# rf24-prueba12-F.net
KiCad netlist of a schematic drawn in EAGLE
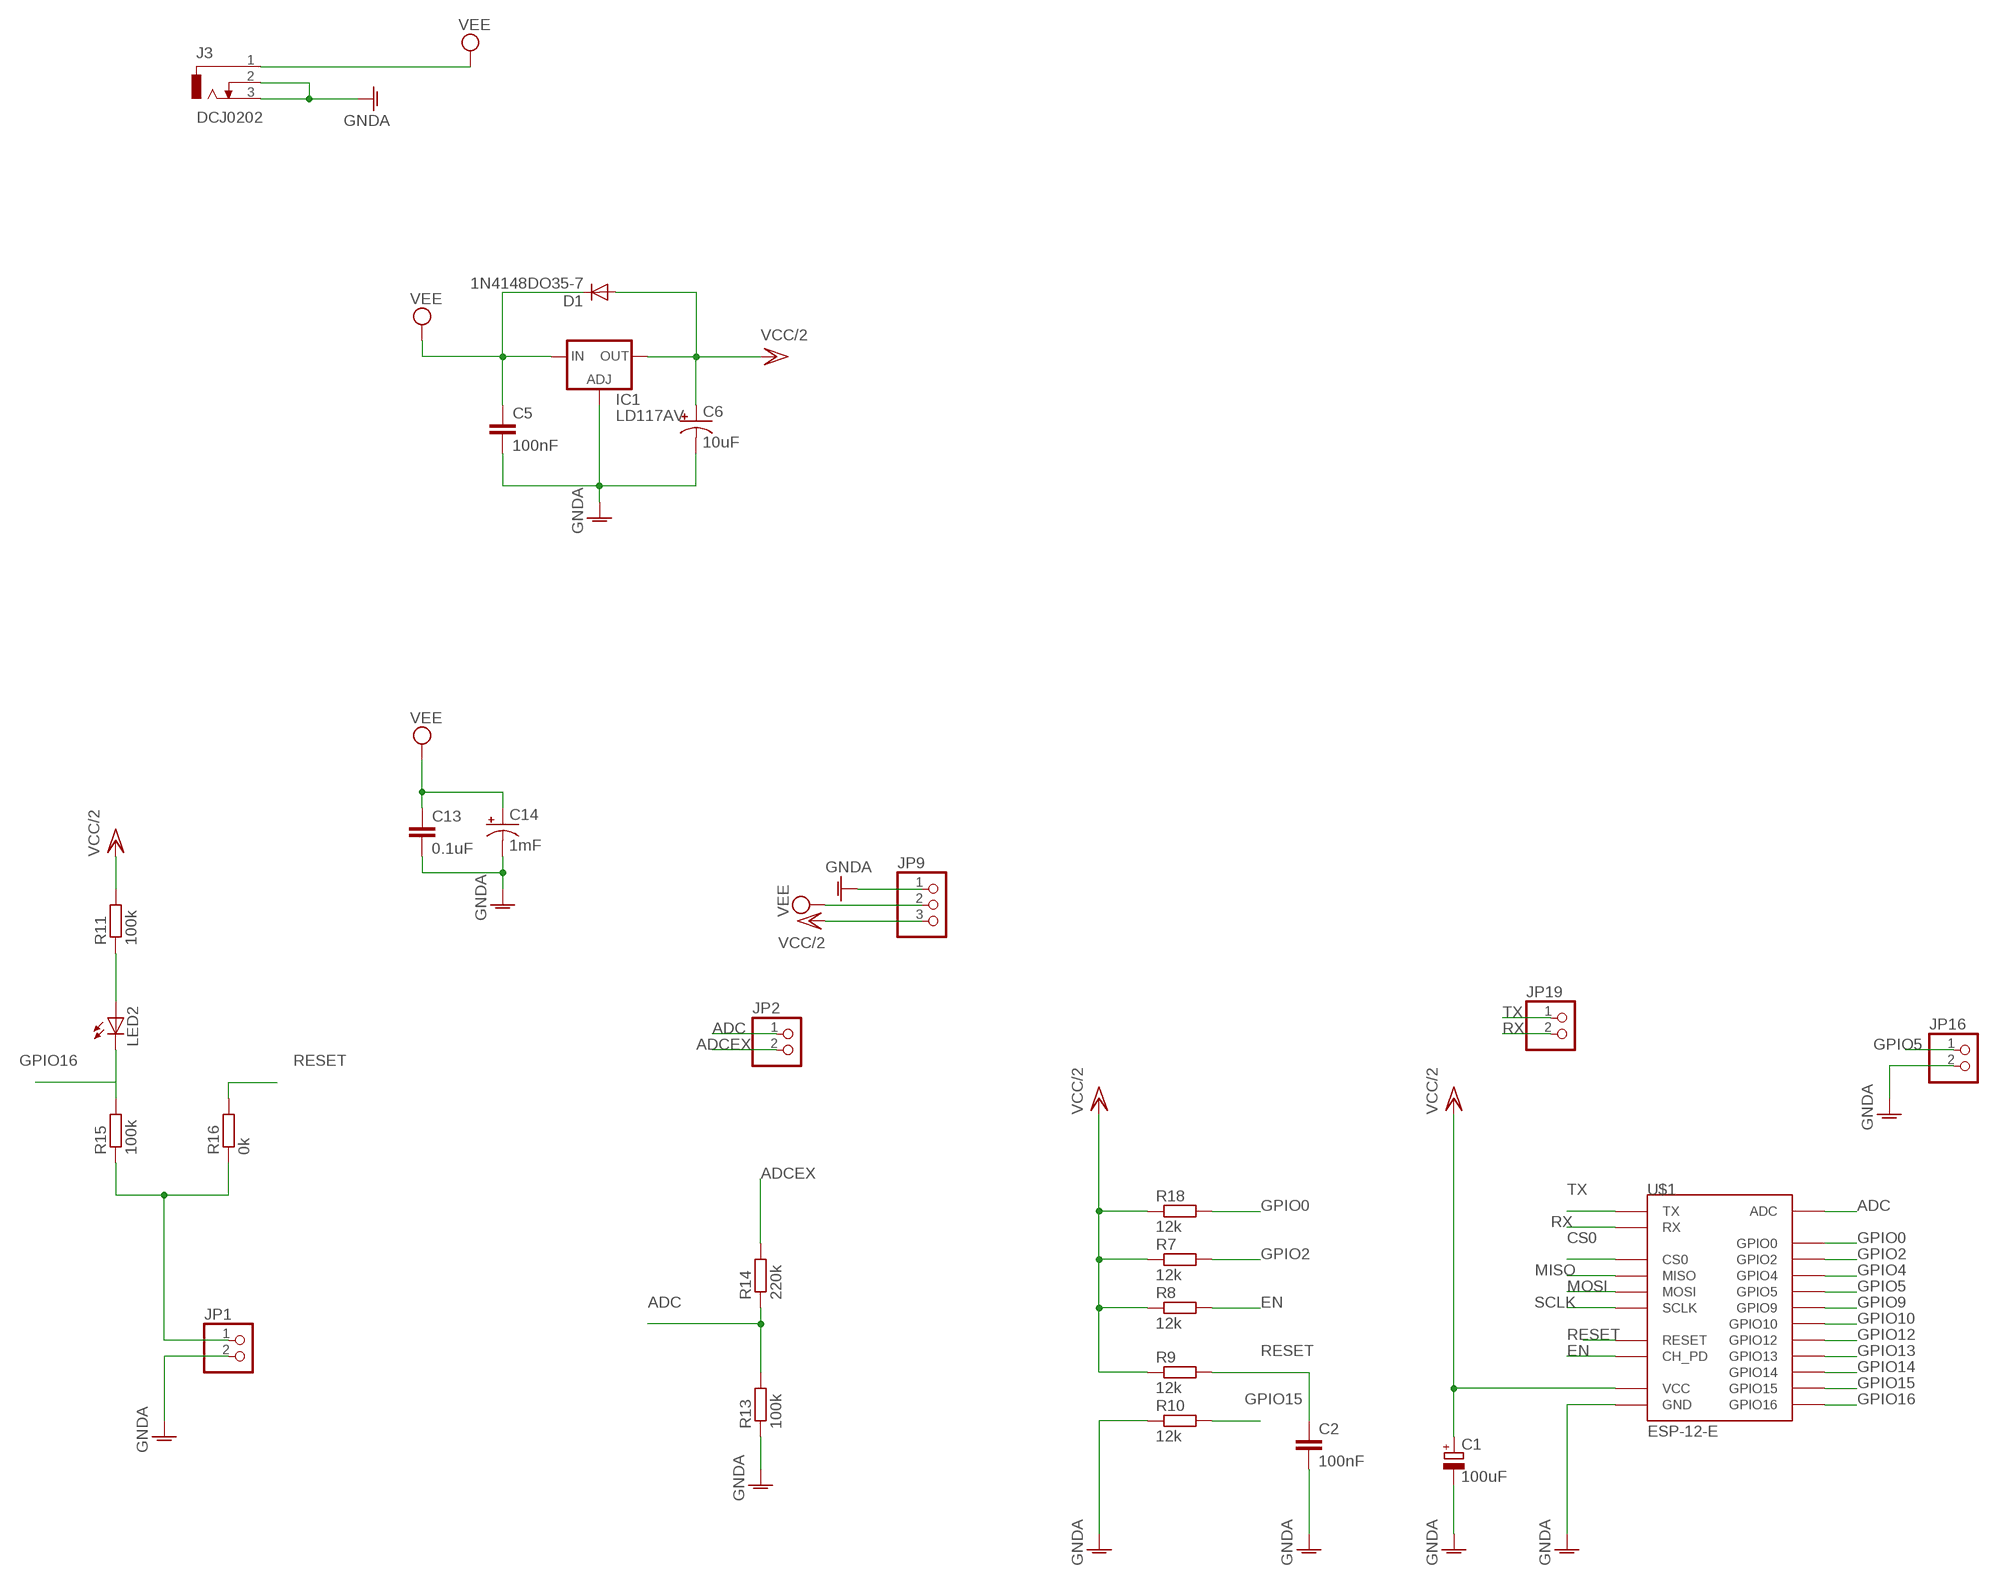
[diagram p0: schematic, sheet 1, part 1 of 2]
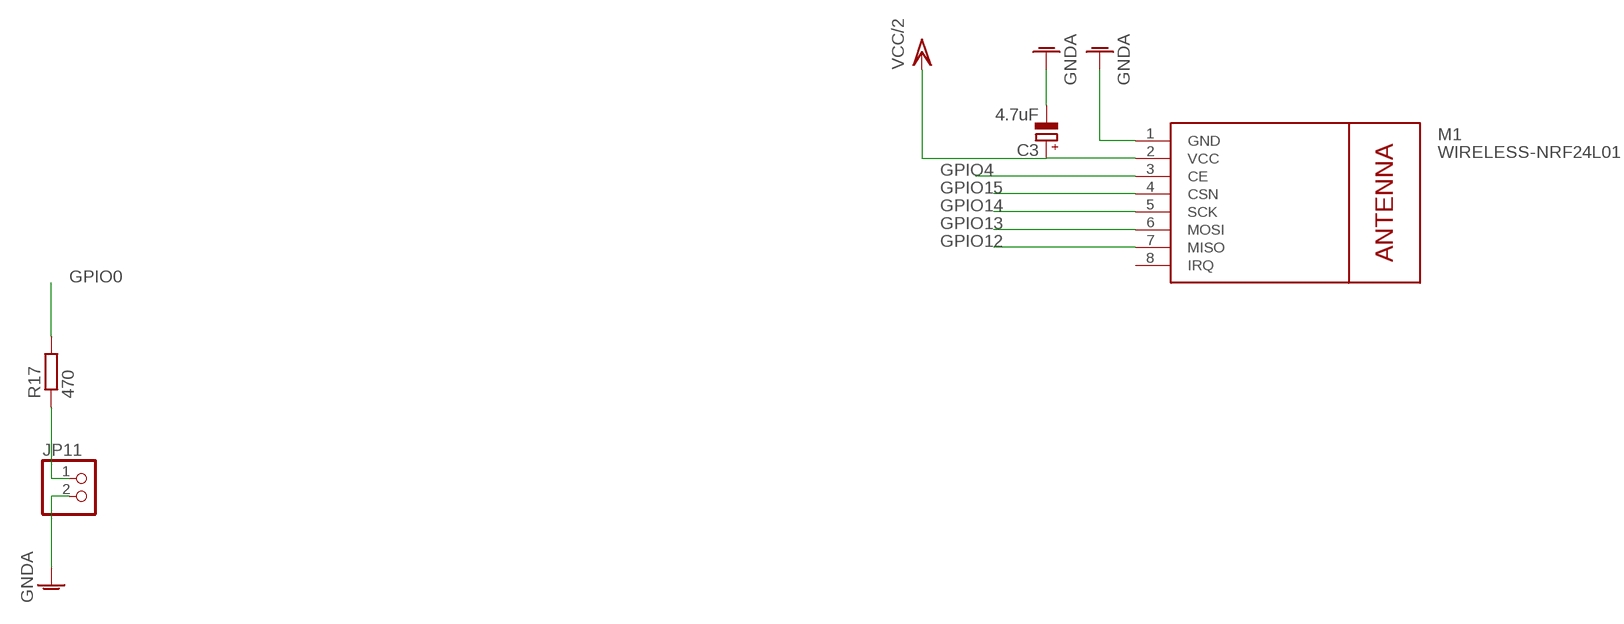
[diagram p1: schematic, sheet 1, part 2 of 2]

(export (version "E")
  (design (tool "Eeschema 10.0.6"))
  (components
    (comp (ref "C1")
      (value "100uF")
      (footprint "eagle-import:TT5D7")
      (libsource (lib "eagle-import") (part "CPOL-EUTT5D7"))
    )
    (comp (ref "C2")
      (value "100nF")
      (footprint "eagle-import:C025-024X044")
      (libsource (lib "eagle-import") (part "C-EU025-024X044"))
    )
    (comp (ref "C3")
      (value "4.7uF")
      (footprint "eagle-import:TT5D7")
      (libsource (lib "eagle-import") (part "CPOL-EUTT5D7"))
    )
    (comp (ref "C5")
      (value "100nF")
      (footprint "eagle-import:C025-025X050")
      (libsource (lib "eagle-import") (part "C-EU025-025X050"))
    )
    (comp (ref "C6")
      (value "10uF")
      (footprint "eagle-import:E2,5-6E")
      (libsource (lib "eagle-import") (part "CPOL-USE2,5-6E"))
    )
    (comp (ref "C13")
      (value "0.1uF")
      (footprint "eagle-import:C025-025X050")
      (libsource (lib "eagle-import") (part "C-EU025-025X050"))
    )
    (comp (ref "C14")
      (value "1mF")
      (footprint "eagle-import:E2,5-6E")
      (libsource (lib "eagle-import") (part "CPOL-USE2,5-6E"))
    )
    (comp (ref "D1")
      (value "1N4148DO35-7")
      (footprint "eagle-import:DO35-7")
      (libsource (lib "eagle-import") (part "1N4148DO35-7"))
    )
    (comp (ref "IC1")
      (value "LD117AV")
      (footprint "eagle-import:TO220L1")
      (libsource (lib "eagle-import") (part "LD117A?V"))
    )
    (comp (ref "J3")
      (value "DCJ0202")
      (footprint "eagle-import:DCJ0202")
      (libsource (lib "eagle-import") (part "DCJ0202"))
    )
    (comp (ref "JP1")
      (value "PINHD-1X2")
      (footprint "eagle-import:1X02")
      (libsource (lib "eagle-import") (part "PINHD-1X2"))
    )
    (comp (ref "JP2")
      (value "PINHD-1X2")
      (footprint "eagle-import:1X02")
      (libsource (lib "eagle-import") (part "PINHD-1X2"))
    )
    (comp (ref "JP9")
      (value "PINHD-1X3")
      (footprint "eagle-import:1X03")
      (libsource (lib "eagle-import") (part "PINHD-1X3"))
    )
    (comp (ref "JP11")
      (value "PINHD-1X2")
      (footprint "eagle-import:1X02")
      (libsource (lib "eagle-import") (part "PINHD-1X2"))
    )
    (comp (ref "JP16")
      (value "PINHD-1X2")
      (footprint "eagle-import:1X02")
      (libsource (lib "eagle-import") (part "PINHD-1X2"))
    )
    (comp (ref "JP19")
      (value "PINHD-1X2")
      (footprint "eagle-import:1X02")
      (libsource (lib "eagle-import") (part "PINHD-1X2"))
    )
    (comp (ref "LED2")
      (value "LED3MM")
      (footprint "eagle-import:LED3MM")
      (libsource (lib "eagle-import") (part "LED3MM"))
    )
    (comp (ref "M1")
      (value "WIRELESS-NRF24L01")
      (footprint "eagle-import:WIRELESS-NRF24L01")
      (libsource (lib "eagle-import") (part "WIRELESS-NRF24L01"))
    )
    (comp (ref "R7")
      (value "12k")
      (footprint "eagle-import:0207_7")
      (libsource (lib "eagle-import") (part "R-EU_0207/7"))
    )
    (comp (ref "R8")
      (value "12k")
      (footprint "eagle-import:0207_7")
      (libsource (lib "eagle-import") (part "R-EU_0207/7"))
    )
    (comp (ref "R9")
      (value "12k")
      (footprint "eagle-import:0207_7")
      (libsource (lib "eagle-import") (part "R-EU_0207/7"))
    )
    (comp (ref "R10")
      (value "12k")
      (footprint "eagle-import:0207_7")
      (libsource (lib "eagle-import") (part "R-EU_0207/7"))
    )
    (comp (ref "R11")
      (value "100k")
      (footprint "eagle-import:0207_7")
      (libsource (lib "eagle-import") (part "R-EU_0207/7"))
    )
    (comp (ref "R13")
      (value "100k")
      (footprint "eagle-import:0207_7")
      (libsource (lib "eagle-import") (part "R-EU_0207/7"))
    )
    (comp (ref "R14")
      (value "220k")
      (footprint "eagle-import:0207_7")
      (libsource (lib "eagle-import") (part "R-EU_0207/7"))
    )
    (comp (ref "R15")
      (value "100k")
      (footprint "eagle-import:0207_7")
      (libsource (lib "eagle-import") (part "R-EU_0207/7"))
    )
    (comp (ref "R16")
      (value "0k")
      (footprint "eagle-import:0207_7")
      (libsource (lib "eagle-import") (part "R-EU_0207/7"))
    )
    (comp (ref "R17")
      (value "470")
      (footprint "eagle-import:0207_7")
      (libsource (lib "eagle-import") (part "R-EU_0207/7"))
    )
    (comp (ref "R18")
      (value "12k")
      (footprint "eagle-import:0207_7")
      (libsource (lib "eagle-import") (part "R-EU_0207/7"))
    )
    (comp (ref "U$1")
      (value "ESP-12-E")
      (footprint "eagle-import:ESP-12-E")
      (fields (field (name "SPICEPREFIX") "X"))
      (libsource (lib "eagle-import") (part "ESP-12-E"))
    )
  )
  (nets
    (net (code "1") (name "/ADC") (class "Default")
      (node (ref "JP2") (pin "1") (pinfunction "1_1") (pintype "passive"))
      (node (ref "R13") (pin "2") (pinfunction "2_2") (pintype "passive"))
      (node (ref "R14") (pin "1") (pinfunction "1_1") (pintype "passive"))
      (node (ref "U$1") (pin "ADC") (pinfunction "ADC_ADC") (pintype "bidirectional"))
    )
    (net (code "2") (name "/ADCEX") (class "Default")
      (node (ref "JP2") (pin "2") (pinfunction "2_2") (pintype "passive"))
      (node (ref "R14") (pin "2") (pinfunction "2_2") (pintype "passive"))
    )
    (net (code "3") (name "/CS0") (class "Default")
      (node (ref "U$1") (pin "CS0") (pinfunction "CS0_CS0") (pintype "bidirectional"))
    )
    (net (code "4") (name "/EN") (class "Default")
      (node (ref "R8") (pin "2") (pinfunction "2_2") (pintype "passive"))
      (node (ref "U$1") (pin "CH_PD") (pinfunction "CH_PD_CH_PD") (pintype "bidirectional"))
    )
    (net (code "5") (name "/GPIO0") (class "Default")
      (node (ref "R17") (pin "2") (pinfunction "2_2") (pintype "passive"))
      (node (ref "R18") (pin "2") (pinfunction "2_2") (pintype "passive"))
      (node (ref "U$1") (pin "GPIO0") (pinfunction "GPIO0_GPIO0") (pintype "bidirectional"))
    )
    (net (code "6") (name "/GPIO2") (class "Default")
      (node (ref "R7") (pin "2") (pinfunction "2_2") (pintype "passive"))
      (node (ref "U$1") (pin "GPIO2") (pinfunction "GPIO2_GPIO2") (pintype "bidirectional"))
    )
    (net (code "7") (name "/GPIO4") (class "Default")
      (node (ref "M1") (pin "3") (pinfunction "CE_3") (pintype "bidirectional"))
      (node (ref "U$1") (pin "GPIO4") (pinfunction "GPIO4_GPIO4") (pintype "bidirectional"))
    )
    (net (code "8") (name "/GPIO5") (class "Default")
      (node (ref "JP16") (pin "1") (pinfunction "1_1") (pintype "passive"))
      (node (ref "U$1") (pin "GPIO5") (pinfunction "GPIO5_GPIO5") (pintype "bidirectional"))
    )
    (net (code "9") (name "/GPIO9") (class "Default")
      (node (ref "U$1") (pin "GPIO9") (pinfunction "GPIO9_GPIO9") (pintype "bidirectional"))
    )
    (net (code "10") (name "/GPIO10") (class "Default")
      (node (ref "U$1") (pin "GPIO10") (pinfunction "GPIO10_GPIO10") (pintype "bidirectional"))
    )
    (net (code "11") (name "/GPIO12") (class "Default")
      (node (ref "M1") (pin "7") (pinfunction "MISO_7") (pintype "bidirectional"))
      (node (ref "U$1") (pin "GPIO12") (pinfunction "GPIO12_GPIO12") (pintype "bidirectional"))
    )
    (net (code "12") (name "/GPIO13") (class "Default")
      (node (ref "M1") (pin "6") (pinfunction "MOSI_6") (pintype "bidirectional"))
      (node (ref "U$1") (pin "GPIO13") (pinfunction "GPIO13_GPIO13") (pintype "bidirectional"))
    )
    (net (code "13") (name "/GPIO14") (class "Default")
      (node (ref "M1") (pin "5") (pinfunction "SCK_5") (pintype "bidirectional"))
      (node (ref "U$1") (pin "GPIO14") (pinfunction "GPIO14_GPIO14") (pintype "bidirectional"))
    )
    (net (code "14") (name "/GPIO15") (class "Default")
      (node (ref "M1") (pin "4") (pinfunction "CSN_4") (pintype "bidirectional"))
      (node (ref "R10") (pin "2") (pinfunction "2_2") (pintype "passive"))
      (node (ref "U$1") (pin "GPIO15") (pinfunction "GPIO15_GPIO15") (pintype "bidirectional"))
    )
    (net (code "15") (name "/GPIO16") (class "Default")
      (node (ref "LED2") (pin "K") (pinfunction "C_K") (pintype "passive"))
      (node (ref "R15") (pin "2") (pinfunction "2_2") (pintype "passive"))
      (node (ref "U$1") (pin "GPIO16") (pinfunction "GPIO16_GPIO16") (pintype "bidirectional"))
    )
    (net (code "16") (name "/MISO") (class "Default")
      (node (ref "U$1") (pin "MISO") (pinfunction "MISO_MISO") (pintype "bidirectional"))
    )
    (net (code "17") (name "/MOSI") (class "Default")
      (node (ref "U$1") (pin "MOSI") (pinfunction "MOSI_MOSI") (pintype "bidirectional"))
    )
    (net (code "18") (name "/RESET") (class "Default")
      (node (ref "C2") (pin "1") (pinfunction "1_1") (pintype "passive"))
      (node (ref "R16") (pin "2") (pinfunction "2_2") (pintype "passive"))
      (node (ref "R9") (pin "2") (pinfunction "2_2") (pintype "passive"))
      (node (ref "U$1") (pin "RESET") (pinfunction "RESET_RESET") (pintype "bidirectional"))
    )
    (net (code "19") (name "/RX") (class "Default")
      (node (ref "JP19") (pin "2") (pinfunction "2_2") (pintype "passive"))
      (node (ref "U$1") (pin "RX") (pinfunction "RX_RX") (pintype "bidirectional"))
    )
    (net (code "20") (name "/SCLK") (class "Default")
      (node (ref "U$1") (pin "SCLK") (pinfunction "SCLK_SCLK") (pintype "bidirectional"))
    )
    (net (code "21") (name "/TX") (class "Default")
      (node (ref "JP19") (pin "1") (pinfunction "1_1") (pintype "passive"))
      (node (ref "U$1") (pin "TX") (pinfunction "TX_TX") (pintype "bidirectional"))
    )
    (net (code "22") (name "GNDA") (class "Default")
      (node (ref "C1") (pin "-") (pinfunction "-_-") (pintype "passive"))
      (node (ref "C13") (pin "2") (pinfunction "2_2") (pintype "passive"))
      (node (ref "C14") (pin "-") (pinfunction "-_-") (pintype "passive"))
      (node (ref "C2") (pin "2") (pinfunction "2_2") (pintype "passive"))
      (node (ref "C3") (pin "-") (pinfunction "-_-") (pintype "passive"))
      (node (ref "C5") (pin "2") (pinfunction "2_2") (pintype "passive"))
      (node (ref "C6") (pin "-") (pinfunction "-_-") (pintype "passive"))
      (node (ref "IC1") (pin "1") (pinfunction "ADJ_1") (pintype "input"))
      (node (ref "J3") (pin "2") (pinfunction "2_2") (pintype "passive"))
      (node (ref "J3") (pin "3") (pinfunction "3_3") (pintype "passive"))
      (node (ref "JP1") (pin "2") (pinfunction "2_2") (pintype "passive"))
      (node (ref "JP11") (pin "2") (pinfunction "2_2") (pintype "passive"))
      (node (ref "JP16") (pin "2") (pinfunction "2_2") (pintype "passive"))
      (node (ref "JP9") (pin "1") (pinfunction "1_1") (pintype "passive"))
      (node (ref "M1") (pin "1") (pinfunction "GND_1") (pintype "power_in"))
      (node (ref "R10") (pin "1") (pinfunction "1_1") (pintype "passive"))
      (node (ref "R13") (pin "1") (pinfunction "1_1") (pintype "passive"))
      (node (ref "U$1") (pin "GND") (pinfunction "GND_GND") (pintype "bidirectional"))
    )
    (net (code "23") (name "Net-(JP1-Pad1)") (class "Default")
      (node (ref "JP1") (pin "1") (pinfunction "1_1") (pintype "passive"))
      (node (ref "R15") (pin "1") (pinfunction "1_1") (pintype "passive"))
      (node (ref "R16") (pin "1") (pinfunction "1_1") (pintype "passive"))
    )
    (net (code "24") (name "Net-(JP11-Pad1)") (class "Default")
      (node (ref "JP11") (pin "1") (pinfunction "1_1") (pintype "passive"))
      (node (ref "R17") (pin "1") (pinfunction "1_1") (pintype "passive"))
    )
    (net (code "25") (name "Net-(LED2-PadA)") (class "Default")
      (node (ref "LED2") (pin "A") (pinfunction "A_A") (pintype "passive"))
      (node (ref "R11") (pin "1") (pinfunction "1_1") (pintype "passive"))
    )
    (net (code "26") (name "VCC{slash}2") (class "Default")
      (node (ref "C1") (pin "+") (pinfunction "+_+") (pintype "passive"))
      (node (ref "C3") (pin "+") (pinfunction "+_+") (pintype "passive"))
      (node (ref "C6") (pin "+") (pinfunction "+_+") (pintype "passive"))
      (node (ref "D1") (pin "A") (pinfunction "A_A") (pintype "passive"))
      (node (ref "IC1") (pin "2") (pinfunction "OUT_2") (pintype "passive"))
      (node (ref "JP9") (pin "3") (pinfunction "3_3") (pintype "passive"))
      (node (ref "M1") (pin "2") (pinfunction "VCC_2") (pintype "power_in"))
      (node (ref "R11") (pin "2") (pinfunction "2_2") (pintype "passive"))
      (node (ref "R18") (pin "1") (pinfunction "1_1") (pintype "passive"))
      (node (ref "R7") (pin "1") (pinfunction "1_1") (pintype "passive"))
      (node (ref "R8") (pin "1") (pinfunction "1_1") (pintype "passive"))
      (node (ref "R9") (pin "1") (pinfunction "1_1") (pintype "passive"))
      (node (ref "U$1") (pin "VCC") (pinfunction "VCC_VCC") (pintype "bidirectional"))
    )
    (net (code "27") (name "VEE") (class "Default")
      (node (ref "C13") (pin "1") (pinfunction "1_1") (pintype "passive"))
      (node (ref "C14") (pin "+") (pinfunction "+_+") (pintype "passive"))
      (node (ref "C5") (pin "1") (pinfunction "1_1") (pintype "passive"))
      (node (ref "D1") (pin "C") (pinfunction "C_C") (pintype "passive"))
      (node (ref "IC1") (pin "3") (pinfunction "IN_3") (pintype "input"))
      (node (ref "J3") (pin "1") (pinfunction "1_1") (pintype "passive"))
      (node (ref "JP9") (pin "2") (pinfunction "2_2") (pintype "passive"))
    )
    (net (code "28") (name "unconnected-(M1-IRQ-Pad8)") (class "Default")
      (node (ref "M1") (pin "8") (pinfunction "IRQ_8") (pintype "bidirectional"))
    )
  )
)
